# fe1_1s_schematic.net
KiCad netlist of a schematic drawn in EAGLE
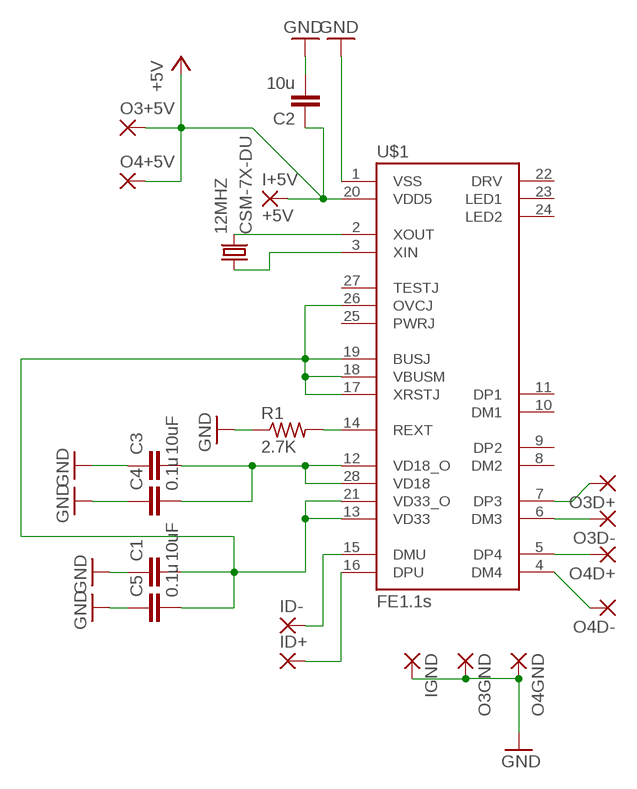
[diagram p0: schematic, sheet 1]

(export (version "E")
  (design (tool "Eeschema 10.0.6"))
  (components
    (comp (ref "12MHZ")
      (value "CSM-7X-DU")
      (footprint "eagle-import:CSM-7X-DU")
      (libsource (lib "eagle-import") (part "CSM-7X-DU"))
    )
    (comp (ref "C1")
      (value "10uF")
      (footprint "eagle-import:C0603")
      (libsource (lib "eagle-import") (part "C-EUC0603"))
    )
    (comp (ref "C2")
      (value "10u")
      (footprint "eagle-import:C0603")
      (libsource (lib "eagle-import") (part "C-EUC0603"))
    )
    (comp (ref "C3")
      (value "10uF")
      (footprint "eagle-import:C0603")
      (libsource (lib "eagle-import") (part "C-EUC0603"))
    )
    (comp (ref "C4")
      (value "0.1u")
      (footprint "eagle-import:C0603")
      (libsource (lib "eagle-import") (part "C-EUC0603"))
    )
    (comp (ref "C5")
      (value "0.1u")
      (footprint "eagle-import:C0603")
      (libsource (lib "eagle-import") (part "C-EUC0603"))
    )
    (comp (ref "I+5V")
      (value "+5V")
      (footprint "eagle-import:1,6_0,8")
      (libsource (lib "eagle-import") (part "1,6/0,8"))
    )
    (comp (ref "ID+")
      (value "1,6/0,8")
      (footprint "eagle-import:1,6_0,8")
      (libsource (lib "eagle-import") (part "1,6/0,8"))
    )
    (comp (ref "ID-")
      (value "1,6/0,8")
      (footprint "eagle-import:1,6_0,8")
      (libsource (lib "eagle-import") (part "1,6/0,8"))
    )
    (comp (ref "IGND")
      (value "1,6/0,8")
      (footprint "eagle-import:1,6_0,8")
      (libsource (lib "eagle-import") (part "1,6/0,8"))
    )
    (comp (ref "O3+5V")
      (value "1,6/0,8")
      (footprint "eagle-import:1,6_0,8")
      (libsource (lib "eagle-import") (part "1,6/0,8"))
    )
    (comp (ref "O3D+")
      (value "1,6/0,8")
      (footprint "eagle-import:1,6_0,8")
      (libsource (lib "eagle-import") (part "1,6/0,8"))
    )
    (comp (ref "O3D-")
      (value "1,6/0,8")
      (footprint "eagle-import:1,6_0,8")
      (libsource (lib "eagle-import") (part "1,6/0,8"))
    )
    (comp (ref "O3GND")
      (value "1,6/0,8")
      (footprint "eagle-import:1,6_0,8")
      (libsource (lib "eagle-import") (part "1,6/0,8"))
    )
    (comp (ref "O4+5V")
      (value "1,6/0,8")
      (footprint "eagle-import:1,6_0,8")
      (libsource (lib "eagle-import") (part "1,6/0,8"))
    )
    (comp (ref "O4D+")
      (value "1,6/0,8")
      (footprint "eagle-import:1,6_0,8")
      (libsource (lib "eagle-import") (part "1,6/0,8"))
    )
    (comp (ref "O4D-")
      (value "1,6/0,8")
      (footprint "eagle-import:1,6_0,8")
      (libsource (lib "eagle-import") (part "1,6/0,8"))
    )
    (comp (ref "O4GND")
      (value "1,6/0,8")
      (footprint "eagle-import:1,6_0,8")
      (libsource (lib "eagle-import") (part "1,6/0,8"))
    )
    (comp (ref "R1")
      (value "2.7K")
      (footprint "eagle-import:R0603")
      (libsource (lib "eagle-import") (part "R-US_R0603"))
    )
    (comp (ref "U$1")
      (value "FE1.1S")
      (footprint "eagle-import:FE1.1S_SSOP-28")
      (libsource (lib "eagle-import") (part "FE1.1S"))
    )
  )
  (nets
    (net (code "1") (name "+5V") (class "Default")
      (node (ref "C2") (pin "1") (pinfunction "1_1") (pintype "passive"))
      (node (ref "I+5V") (pin "1") (pinfunction "P_1") (pintype "passive"))
      (node (ref "O3+5V") (pin "1") (pinfunction "P_1") (pintype "passive"))
      (node (ref "O4+5V") (pin "1") (pinfunction "P_1") (pintype "passive"))
      (node (ref "U$1") (pin "20") (pinfunction "VDD5_20") (pintype "bidirectional"))
    )
    (net (code "2") (name "GND") (class "Default")
      (node (ref "C1") (pin "1") (pinfunction "1_1") (pintype "passive"))
      (node (ref "C2") (pin "2") (pinfunction "2_2") (pintype "passive"))
      (node (ref "C3") (pin "1") (pinfunction "1_1") (pintype "passive"))
      (node (ref "C4") (pin "1") (pinfunction "1_1") (pintype "passive"))
      (node (ref "C5") (pin "1") (pinfunction "1_1") (pintype "passive"))
      (node (ref "IGND") (pin "1") (pinfunction "P_1") (pintype "passive"))
      (node (ref "O3GND") (pin "1") (pinfunction "P_1") (pintype "passive"))
      (node (ref "O4GND") (pin "1") (pinfunction "P_1") (pintype "passive"))
      (node (ref "R1") (pin "1") (pinfunction "1_1") (pintype "passive"))
      (node (ref "U$1") (pin "1") (pinfunction "VSS_1") (pintype "bidirectional"))
    )
    (net (code "3") (name "Net-(ID+-P)") (class "Default")
      (node (ref "ID+") (pin "1") (pinfunction "P_1") (pintype "passive"))
      (node (ref "U$1") (pin "16") (pinfunction "DPU_16") (pintype "bidirectional"))
    )
    (net (code "4") (name "Net-(ID--P)") (class "Default")
      (node (ref "ID-") (pin "1") (pinfunction "P_1") (pintype "passive"))
      (node (ref "U$1") (pin "15") (pinfunction "DMU_15") (pintype "bidirectional"))
    )
    (net (code "5") (name "Net-(O3D+-P)") (class "Default")
      (node (ref "O3D+") (pin "1") (pinfunction "P_1") (pintype "passive"))
      (node (ref "U$1") (pin "7") (pinfunction "DP3_7") (pintype "bidirectional"))
    )
    (net (code "6") (name "Net-(O3D--P)") (class "Default")
      (node (ref "O3D-") (pin "1") (pinfunction "P_1") (pintype "passive"))
      (node (ref "U$1") (pin "6") (pinfunction "DM3_6") (pintype "bidirectional"))
    )
    (net (code "7") (name "Net-(O4D+-P)") (class "Default")
      (node (ref "O4D+") (pin "1") (pinfunction "P_1") (pintype "passive"))
      (node (ref "U$1") (pin "5") (pinfunction "DP4_5") (pintype "bidirectional"))
    )
    (net (code "8") (name "Net-(O4D--P)") (class "Default")
      (node (ref "O4D-") (pin "1") (pinfunction "P_1") (pintype "passive"))
      (node (ref "U$1") (pin "4") (pinfunction "DM4_4") (pintype "bidirectional"))
    )
    (net (code "9") (name "Net-(U$1-BUSJ)") (class "Default")
      (node (ref "C1") (pin "2") (pinfunction "2_2") (pintype "passive"))
      (node (ref "C5") (pin "2") (pinfunction "2_2") (pintype "passive"))
      (node (ref "U$1") (pin "13") (pinfunction "VD33_13") (pintype "bidirectional"))
      (node (ref "U$1") (pin "17") (pinfunction "XRSTJ_17") (pintype "bidirectional"))
      (node (ref "U$1") (pin "18") (pinfunction "VBUSM_18") (pintype "bidirectional"))
      (node (ref "U$1") (pin "19") (pinfunction "BUSJ_19") (pintype "bidirectional"))
      (node (ref "U$1") (pin "21") (pinfunction "VD33_O_21") (pintype "bidirectional"))
      (node (ref "U$1") (pin "26") (pinfunction "OVCJ_26") (pintype "bidirectional"))
    )
    (net (code "10") (name "Net-(U$1-REXT)") (class "Default")
      (node (ref "R1") (pin "2") (pinfunction "2_2") (pintype "passive"))
      (node (ref "U$1") (pin "14") (pinfunction "REXT_14") (pintype "bidirectional"))
    )
    (net (code "11") (name "Net-(U$1-VD18)") (class "Default")
      (node (ref "C3") (pin "2") (pinfunction "2_2") (pintype "passive"))
      (node (ref "C4") (pin "2") (pinfunction "2_2") (pintype "passive"))
      (node (ref "U$1") (pin "12") (pinfunction "VD18_O_12") (pintype "bidirectional"))
      (node (ref "U$1") (pin "28") (pinfunction "VD18_28") (pintype "bidirectional"))
    )
    (net (code "12") (name "Net-(U$1-XIN)") (class "Default")
      (node (ref "12MHZ") (pin "1") (pinfunction "1_1") (pintype "passive"))
      (node (ref "U$1") (pin "3") (pinfunction "XIN_3") (pintype "bidirectional"))
    )
    (net (code "13") (name "Net-(U$1-XOUT)") (class "Default")
      (node (ref "12MHZ") (pin "2") (pinfunction "2_2") (pintype "passive"))
      (node (ref "U$1") (pin "2") (pinfunction "XOUT_2") (pintype "bidirectional"))
    )
    (net (code "14") (name "unconnected-(U$1-DM1-Pad10)") (class "Default")
      (node (ref "U$1") (pin "10") (pinfunction "DM1_10") (pintype "bidirectional"))
    )
    (net (code "15") (name "unconnected-(U$1-DM2-Pad8)") (class "Default")
      (node (ref "U$1") (pin "8") (pinfunction "DM2_8") (pintype "bidirectional"))
    )
    (net (code "16") (name "unconnected-(U$1-DP1-Pad11)") (class "Default")
      (node (ref "U$1") (pin "11") (pinfunction "DP1_11") (pintype "bidirectional"))
    )
    (net (code "17") (name "unconnected-(U$1-DP2-Pad9)") (class "Default")
      (node (ref "U$1") (pin "9") (pinfunction "DP2_9") (pintype "bidirectional"))
    )
    (net (code "18") (name "unconnected-(U$1-DRV-Pad22)") (class "Default")
      (node (ref "U$1") (pin "22") (pinfunction "DRV_22") (pintype "bidirectional"))
    )
    (net (code "19") (name "unconnected-(U$1-LED1-Pad23)") (class "Default")
      (node (ref "U$1") (pin "23") (pinfunction "LED1_23") (pintype "bidirectional"))
    )
    (net (code "20") (name "unconnected-(U$1-LED2-Pad24)") (class "Default")
      (node (ref "U$1") (pin "24") (pinfunction "LED2_24") (pintype "bidirectional"))
    )
    (net (code "21") (name "unconnected-(U$1-PWRJ-Pad25)") (class "Default")
      (node (ref "U$1") (pin "25") (pinfunction "PWRJ_25") (pintype "bidirectional"))
    )
    (net (code "22") (name "unconnected-(U$1-TESTJ-Pad27)") (class "Default")
      (node (ref "U$1") (pin "27") (pinfunction "TESTJ_27") (pintype "bidirectional"))
    )
  )
)
